# electrical_circut_clock.net
KiCad netlist of a schematic drawn in EAGLE
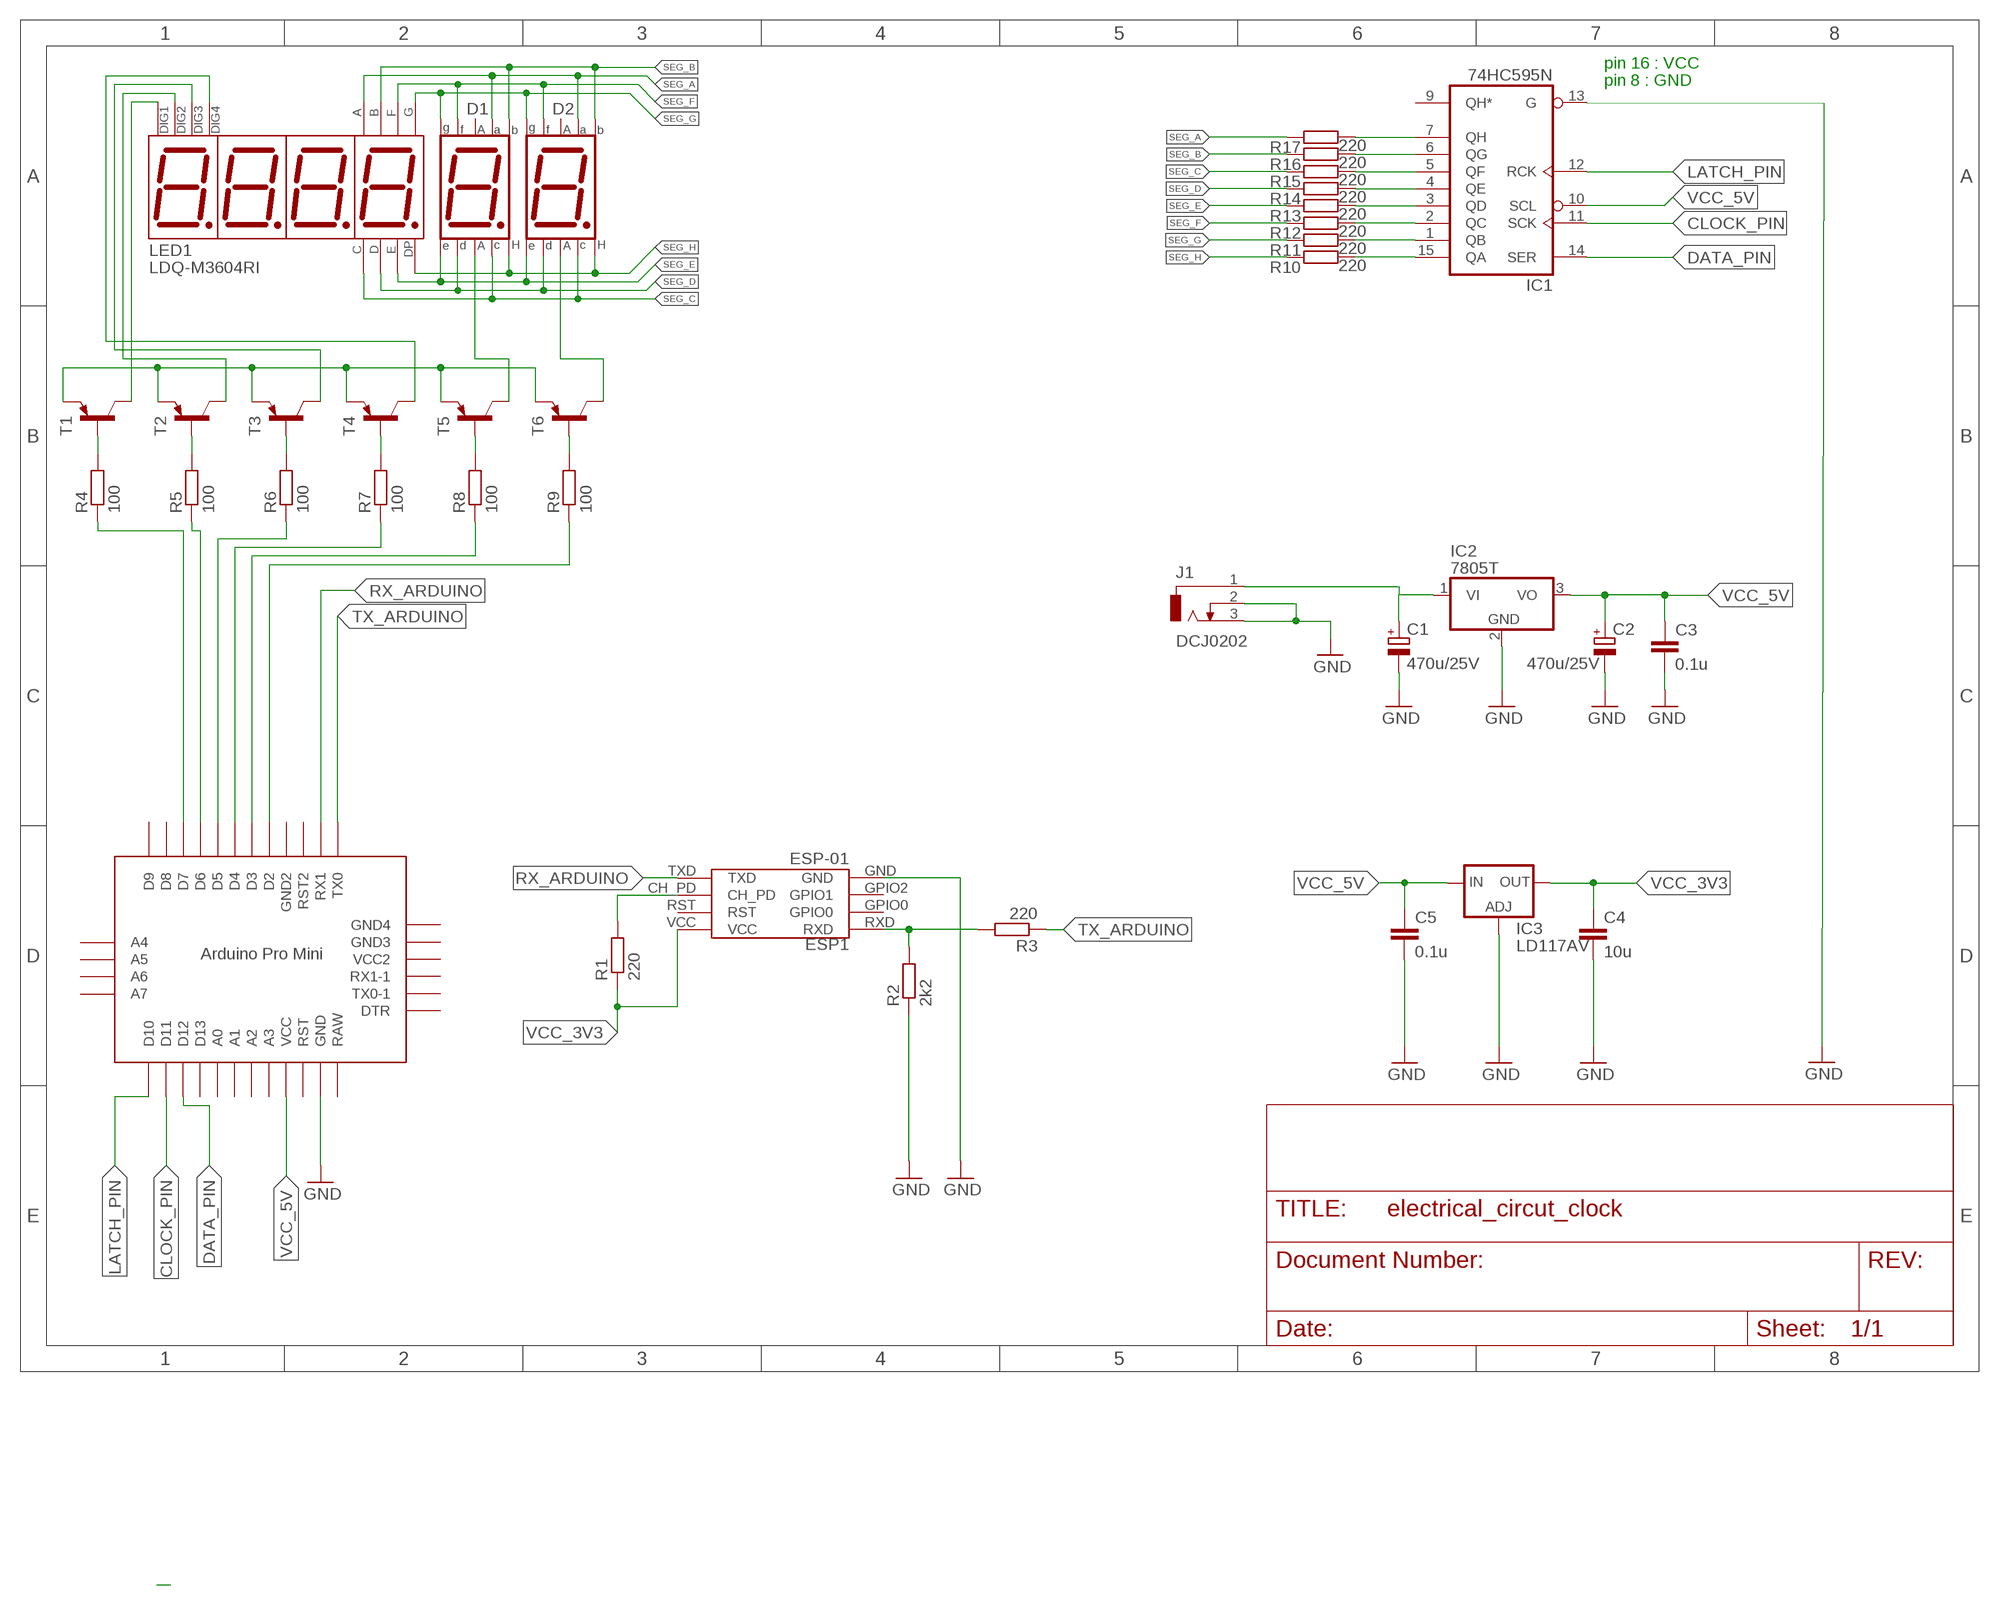
[diagram p0: schematic, sheet 1]

(export (version "E")
  (design (tool "Eeschema 10.0.6"))
  (components
    (comp (ref "C1")
      (value "470u/25V")
      (footprint "eagle-import:E5-8,5")
      (libsource (lib "eagle-import") (part "CPOL-EUE5-8.5"))
    )
    (comp (ref "C2")
      (value "470u/25V")
      (footprint "eagle-import:E5-8,5")
      (libsource (lib "eagle-import") (part "CPOL-EUE5-8.5"))
    )
    (comp (ref "C3")
      (value "0.1u")
      (footprint "eagle-import:C025-025X050")
      (libsource (lib "eagle-import") (part "C-EU025-025X050"))
    )
    (comp (ref "C4")
      (value "10u")
      (footprint "eagle-import:C025-025X050")
      (libsource (lib "eagle-import") (part "C-EU025-025X050"))
    )
    (comp (ref "C5")
      (value "0.1u")
      (footprint "eagle-import:C025-025X050")
      (libsource (lib "eagle-import") (part "C-EU025-025X050"))
    )
    (comp (ref "D1")
      (value "7SEG-CA")
      (footprint "eagle-import:7SEG-13")
      (libsource (lib "eagle-import") (part "7SEG-CA"))
    )
    (comp (ref "D2")
      (value "7SEG-CA")
      (footprint "eagle-import:7SEG-13")
      (libsource (lib "eagle-import") (part "7SEG-CA"))
    )
    (comp (ref "ESP1")
      (value "ESP-01")
      (footprint "eagle-import:ESP-01")
      (fields (field (name "MF") "AI-Thinker"))
      (libsource (lib "eagle-import") (part "ESP-01"))
    )
    (comp (ref "IC1")
      (value "74HC595N")
      (footprint "eagle-import:DIL16")
      (libsource (lib "eagle-import") (part "74595NHC"))
    )
    (comp (ref "IC2")
      (value "7805T")
      (footprint "eagle-import:TO220H")
      (libsource (lib "eagle-import") (part "78T05"))
    )
    (comp (ref "IC3")
      (value "LD117AV")
      (footprint "eagle-import:TO220L1")
      (libsource (lib "eagle-import") (part "LD117A?V"))
    )
    (comp (ref "J1")
      (value "DCJ0202")
      (footprint "eagle-import:DCJ0202")
      (libsource (lib "eagle-import") (part "DCJ0202"))
    )
    (comp (ref "LED1")
      (value "LDQ-M3604RI")
      (footprint "eagle-import:LDQ-M3604RI")
      (fields (field (name "MF") "Lumex"))
      (libsource (lib "eagle-import") (part "LDQ-M3604RI"))
    )
    (comp (ref "R1")
      (value "220")
      (footprint "eagle-import:0204_7")
      (libsource (lib "eagle-import") (part "R-EU_0204/7"))
    )
    (comp (ref "R2")
      (value "2k2")
      (footprint "eagle-import:0204_7")
      (libsource (lib "eagle-import") (part "R-EU_0204/7"))
    )
    (comp (ref "R3")
      (value "220")
      (footprint "eagle-import:0204_7")
      (libsource (lib "eagle-import") (part "R-EU_0204/7"))
    )
    (comp (ref "R4")
      (value "100")
      (footprint "eagle-import:0204_7")
      (libsource (lib "eagle-import") (part "R-EU_0204/7"))
    )
    (comp (ref "R5")
      (value "100")
      (footprint "eagle-import:0204_7")
      (libsource (lib "eagle-import") (part "R-EU_0204/7"))
    )
    (comp (ref "R6")
      (value "100")
      (footprint "eagle-import:0204_7")
      (libsource (lib "eagle-import") (part "R-EU_0204/7"))
    )
    (comp (ref "R7")
      (value "100")
      (footprint "eagle-import:0204_7")
      (libsource (lib "eagle-import") (part "R-EU_0204/7"))
    )
    (comp (ref "R8")
      (value "100")
      (footprint "eagle-import:0204_7")
      (libsource (lib "eagle-import") (part "R-EU_0204/7"))
    )
    (comp (ref "R9")
      (value "100")
      (footprint "eagle-import:0204_7")
      (libsource (lib "eagle-import") (part "R-EU_0204/7"))
    )
    (comp (ref "R10")
      (value "220")
      (footprint "eagle-import:0204_7")
      (libsource (lib "eagle-import") (part "R-EU_0204/7"))
    )
    (comp (ref "R11")
      (value "220")
      (footprint "eagle-import:0204_7")
      (libsource (lib "eagle-import") (part "R-EU_0204/7"))
    )
    (comp (ref "R12")
      (value "220")
      (footprint "eagle-import:0204_7")
      (libsource (lib "eagle-import") (part "R-EU_0204/7"))
    )
    (comp (ref "R13")
      (value "220")
      (footprint "eagle-import:0204_7")
      (libsource (lib "eagle-import") (part "R-EU_0204/7"))
    )
    (comp (ref "R14")
      (value "220")
      (footprint "eagle-import:0204_7")
      (libsource (lib "eagle-import") (part "R-EU_0204/7"))
    )
    (comp (ref "R15")
      (value "220")
      (footprint "eagle-import:0204_7")
      (libsource (lib "eagle-import") (part "R-EU_0204/7"))
    )
    (comp (ref "R16")
      (value "220")
      (footprint "eagle-import:0204_7")
      (libsource (lib "eagle-import") (part "R-EU_0204/7"))
    )
    (comp (ref "R17")
      (value "220")
      (footprint "eagle-import:0204_7")
      (libsource (lib "eagle-import") (part "R-EU_0204/7"))
    )
    (comp (ref "T1")
      (value "BC556A-PNP-TO92-EBC")
      (footprint "eagle-import:TO92-EBC")
      (libsource (lib "eagle-import") (part "-PNP-TO92-EBCBC556A"))
    )
    (comp (ref "T2")
      (value "BC556A-PNP-TO92-EBC")
      (footprint "eagle-import:TO92-EBC")
      (libsource (lib "eagle-import") (part "-PNP-TO92-EBCBC556A"))
    )
    (comp (ref "T3")
      (value "BC556A-PNP-TO92-EBC")
      (footprint "eagle-import:TO92-EBC")
      (libsource (lib "eagle-import") (part "-PNP-TO92-EBCBC556A"))
    )
    (comp (ref "T4")
      (value "BC556A-PNP-TO92-EBC")
      (footprint "eagle-import:TO92-EBC")
      (libsource (lib "eagle-import") (part "-PNP-TO92-EBCBC556A"))
    )
    (comp (ref "T5")
      (value "BC556A-PNP-TO92-EBC")
      (footprint "eagle-import:TO92-EBC")
      (libsource (lib "eagle-import") (part "-PNP-TO92-EBCBC556A"))
    )
    (comp (ref "T6")
      (value "BC556A-PNP-TO92-EBC")
      (footprint "eagle-import:TO92-EBC")
      (libsource (lib "eagle-import") (part "-PNP-TO92-EBCBC556A"))
    )
    (comp (ref "U$1")
      (value "PRO-MINI")
      (footprint "eagle-import:PRO-MINI")
      (libsource (lib "eagle-import") (part "PRO-MINI"))
    )
  )
  (nets
    (net (code "1") (name "/RAW") (class "Default")
      (node (ref "U$1") (pin "RAW") (pinfunction "RAW_RAW") (pintype "power_in"))
    )
    (net (code "2") (name "CLOCK_PIN") (class "Default")
      (node (ref "IC1") (pin "11") (pinfunction "SCK_11") (pintype "input"))
      (node (ref "U$1") (pin "D11") (pinfunction "D11_D11") (pintype "bidirectional"))
    )
    (net (code "3") (name "DATA_PIN") (class "Default")
      (node (ref "IC1") (pin "14") (pinfunction "SER_14") (pintype "input"))
      (node (ref "U$1") (pin "D12") (pinfunction "D12_D12") (pintype "bidirectional"))
    )
    (net (code "4") (name "GND") (class "Default")
      (node (ref "C1") (pin "-") (pinfunction "-_-") (pintype "passive"))
      (node (ref "C2") (pin "-") (pinfunction "-_-") (pintype "passive"))
      (node (ref "C3") (pin "2") (pinfunction "2_2") (pintype "passive"))
      (node (ref "C4") (pin "2") (pinfunction "2_2") (pintype "passive"))
      (node (ref "C5") (pin "2") (pinfunction "2_2") (pintype "passive"))
      (node (ref "ESP1") (pin "GND") (pinfunction "GND_GND") (pintype "bidirectional"))
      (node (ref "IC1") (pin "13") (pinfunction "G_13") (pintype "input"))
      (node (ref "IC2") (pin "2") (pinfunction "GND_2") (pintype "passive"))
      (node (ref "IC3") (pin "1") (pinfunction "ADJ_1") (pintype "input"))
      (node (ref "J1") (pin "2") (pinfunction "2_2") (pintype "passive"))
      (node (ref "J1") (pin "3") (pinfunction "3_3") (pintype "passive"))
      (node (ref "R2") (pin "1") (pinfunction "1_1") (pintype "passive"))
      (node (ref "U$1") (pin "GND") (pinfunction "GND_GND") (pintype "input"))
    )
    (net (code "5") (name "LATCH_PIN") (class "Default")
      (node (ref "IC1") (pin "12") (pinfunction "RCK_12") (pintype "input"))
      (node (ref "U$1") (pin "D10") (pinfunction "D10_D10") (pintype "bidirectional"))
    )
    (net (code "6") (name "Net-(D1-CA2)") (class "Default")
      (node (ref "D1") (pin "8") (pinfunction "CA2_8") (pintype "passive"))
      (node (ref "T5") (pin "C") (pinfunction "C_C") (pintype "passive"))
    )
    (net (code "7") (name "Net-(D2-CA2)") (class "Default")
      (node (ref "D2") (pin "8") (pinfunction "CA2_8") (pintype "passive"))
      (node (ref "T6") (pin "C") (pinfunction "C_C") (pintype "passive"))
    )
    (net (code "8") (name "Net-(ESP1-PadCH_PD)") (class "Default")
      (node (ref "ESP1") (pin "CH_PD") (pinfunction "CH_PD_CH_PD") (pintype "bidirectional"))
      (node (ref "R1") (pin "2") (pinfunction "2_2") (pintype "passive"))
    )
    (net (code "9") (name "Net-(IC1A-QA)") (class "Default")
      (node (ref "IC1") (pin "15") (pinfunction "QA_15") (pintype "tri_state"))
      (node (ref "R10") (pin "2") (pinfunction "2_2") (pintype "passive"))
    )
    (net (code "10") (name "Net-(IC1A-QB)") (class "Default")
      (node (ref "IC1") (pin "1") (pinfunction "QB_1") (pintype "tri_state"))
      (node (ref "R11") (pin "2") (pinfunction "2_2") (pintype "passive"))
    )
    (net (code "11") (name "Net-(IC1A-QC)") (class "Default")
      (node (ref "IC1") (pin "2") (pinfunction "QC_2") (pintype "tri_state"))
      (node (ref "R12") (pin "2") (pinfunction "2_2") (pintype "passive"))
    )
    (net (code "12") (name "Net-(IC1A-QD)") (class "Default")
      (node (ref "IC1") (pin "3") (pinfunction "QD_3") (pintype "tri_state"))
      (node (ref "R13") (pin "2") (pinfunction "2_2") (pintype "passive"))
    )
    (net (code "13") (name "Net-(IC1A-QE)") (class "Default")
      (node (ref "IC1") (pin "4") (pinfunction "QE_4") (pintype "tri_state"))
      (node (ref "R14") (pin "2") (pinfunction "2_2") (pintype "passive"))
    )
    (net (code "14") (name "Net-(IC1A-QF)") (class "Default")
      (node (ref "IC1") (pin "5") (pinfunction "QF_5") (pintype "tri_state"))
      (node (ref "R15") (pin "2") (pinfunction "2_2") (pintype "passive"))
    )
    (net (code "15") (name "Net-(IC1A-QG)") (class "Default")
      (node (ref "IC1") (pin "6") (pinfunction "QG_6") (pintype "tri_state"))
      (node (ref "R16") (pin "2") (pinfunction "2_2") (pintype "passive"))
    )
    (net (code "16") (name "Net-(IC1A-QH)") (class "Default")
      (node (ref "IC1") (pin "7") (pinfunction "QH_7") (pintype "tri_state"))
      (node (ref "R17") (pin "2") (pinfunction "2_2") (pintype "passive"))
    )
    (net (code "17") (name "Net-(IC2-VI)") (class "Default")
      (node (ref "C1") (pin "+") (pinfunction "+_+") (pintype "passive"))
      (node (ref "IC2") (pin "1") (pinfunction "VI_1") (pintype "input"))
      (node (ref "J1") (pin "1") (pinfunction "1_1") (pintype "passive"))
    )
    (net (code "18") (name "Net-(LED1-DIG1)") (class "Default")
      (node (ref "LED1") (pin "12") (pinfunction "DIG1_12") (pintype "bidirectional"))
      (node (ref "T1") (pin "C") (pinfunction "C_C") (pintype "passive"))
    )
    (net (code "19") (name "Net-(LED1-DIG2)") (class "Default")
      (node (ref "LED1") (pin "9") (pinfunction "DIG2_9") (pintype "bidirectional"))
      (node (ref "T2") (pin "C") (pinfunction "C_C") (pintype "passive"))
    )
    (net (code "20") (name "Net-(LED1-DIG3)") (class "Default")
      (node (ref "LED1") (pin "8") (pinfunction "DIG3_8") (pintype "bidirectional"))
      (node (ref "T3") (pin "C") (pinfunction "C_C") (pintype "passive"))
    )
    (net (code "21") (name "Net-(LED1-DIG4)") (class "Default")
      (node (ref "LED1") (pin "6") (pinfunction "DIG4_6") (pintype "bidirectional"))
      (node (ref "T4") (pin "C") (pinfunction "C_C") (pintype "passive"))
    )
    (net (code "22") (name "Net-(R4-Pad1)") (class "Default")
      (node (ref "R4") (pin "1") (pinfunction "1_1") (pintype "passive"))
      (node (ref "U$1") (pin "D7") (pinfunction "D7_D7") (pintype "bidirectional"))
    )
    (net (code "23") (name "Net-(R4-Pad2)") (class "Default")
      (node (ref "R4") (pin "2") (pinfunction "2_2") (pintype "passive"))
      (node (ref "T1") (pin "B") (pinfunction "B_B") (pintype "passive"))
    )
    (net (code "24") (name "Net-(R5-Pad1)") (class "Default")
      (node (ref "R5") (pin "1") (pinfunction "1_1") (pintype "passive"))
      (node (ref "U$1") (pin "D6") (pinfunction "D6_D6") (pintype "bidirectional"))
    )
    (net (code "25") (name "Net-(R5-Pad2)") (class "Default")
      (node (ref "R5") (pin "2") (pinfunction "2_2") (pintype "passive"))
      (node (ref "T2") (pin "B") (pinfunction "B_B") (pintype "passive"))
    )
    (net (code "26") (name "Net-(R6-Pad1)") (class "Default")
      (node (ref "R6") (pin "1") (pinfunction "1_1") (pintype "passive"))
      (node (ref "U$1") (pin "D5") (pinfunction "D5_D5") (pintype "bidirectional"))
    )
    (net (code "27") (name "Net-(R6-Pad2)") (class "Default")
      (node (ref "R6") (pin "2") (pinfunction "2_2") (pintype "passive"))
      (node (ref "T3") (pin "B") (pinfunction "B_B") (pintype "passive"))
    )
    (net (code "28") (name "Net-(R7-Pad1)") (class "Default")
      (node (ref "R7") (pin "1") (pinfunction "1_1") (pintype "passive"))
      (node (ref "U$1") (pin "D4") (pinfunction "D4_D4") (pintype "bidirectional"))
    )
    (net (code "29") (name "Net-(R7-Pad2)") (class "Default")
      (node (ref "R7") (pin "2") (pinfunction "2_2") (pintype "passive"))
      (node (ref "T4") (pin "B") (pinfunction "B_B") (pintype "passive"))
    )
    (net (code "30") (name "Net-(R8-Pad1)") (class "Default")
      (node (ref "R8") (pin "1") (pinfunction "1_1") (pintype "passive"))
      (node (ref "U$1") (pin "D3") (pinfunction "D3_D3") (pintype "bidirectional"))
    )
    (net (code "31") (name "Net-(R8-Pad2)") (class "Default")
      (node (ref "R8") (pin "2") (pinfunction "2_2") (pintype "passive"))
      (node (ref "T5") (pin "B") (pinfunction "B_B") (pintype "passive"))
    )
    (net (code "32") (name "Net-(R9-Pad1)") (class "Default")
      (node (ref "R9") (pin "1") (pinfunction "1_1") (pintype "passive"))
      (node (ref "U$1") (pin "D2") (pinfunction "D2_D2") (pintype "bidirectional"))
    )
    (net (code "33") (name "Net-(R9-Pad2)") (class "Default")
      (node (ref "R9") (pin "2") (pinfunction "2_2") (pintype "passive"))
      (node (ref "T6") (pin "B") (pinfunction "B_B") (pintype "passive"))
    )
    (net (code "34") (name "Net-(T1-PadE)") (class "Default")
      (node (ref "T1") (pin "E") (pinfunction "E_E") (pintype "passive"))
      (node (ref "T2") (pin "E") (pinfunction "E_E") (pintype "passive"))
      (node (ref "T3") (pin "E") (pinfunction "E_E") (pintype "passive"))
      (node (ref "T4") (pin "E") (pinfunction "E_E") (pintype "passive"))
      (node (ref "T5") (pin "E") (pinfunction "E_E") (pintype "passive"))
      (node (ref "T6") (pin "E") (pinfunction "E_E") (pintype "passive"))
    )
    (net (code "35") (name "RX_ARDUINO") (class "Default")
      (node (ref "ESP1") (pin "TXD") (pinfunction "TXD_TXD") (pintype "bidirectional"))
      (node (ref "U$1") (pin "RX1") (pinfunction "RX1_RX1") (pintype "bidirectional"))
    )
    (net (code "36") (name "SEG_A") (class "Default")
      (node (ref "D1") (pin "7") (pinfunction "A_7") (pintype "passive"))
      (node (ref "D2") (pin "7") (pinfunction "A_7") (pintype "passive"))
      (node (ref "LED1") (pin "11") (pinfunction "A_11") (pintype "bidirectional"))
      (node (ref "R17") (pin "1") (pinfunction "1_1") (pintype "passive"))
    )
    (net (code "37") (name "SEG_B") (class "Default")
      (node (ref "D1") (pin "6") (pinfunction "B_6") (pintype "passive"))
      (node (ref "D2") (pin "6") (pinfunction "B_6") (pintype "passive"))
      (node (ref "LED1") (pin "7") (pinfunction "B_7") (pintype "bidirectional"))
      (node (ref "R16") (pin "1") (pinfunction "1_1") (pintype "passive"))
    )
    (net (code "38") (name "SEG_C") (class "Default")
      (node (ref "D1") (pin "4") (pinfunction "C_4") (pintype "passive"))
      (node (ref "D2") (pin "4") (pinfunction "C_4") (pintype "passive"))
      (node (ref "LED1") (pin "4") (pinfunction "C_4") (pintype "bidirectional"))
      (node (ref "R15") (pin "1") (pinfunction "1_1") (pintype "passive"))
    )
    (net (code "39") (name "SEG_D") (class "Default")
      (node (ref "D1") (pin "2") (pinfunction "D_2") (pintype "passive"))
      (node (ref "D2") (pin "2") (pinfunction "D_2") (pintype "passive"))
      (node (ref "LED1") (pin "2") (pinfunction "D_2") (pintype "bidirectional"))
      (node (ref "R14") (pin "1") (pinfunction "1_1") (pintype "passive"))
    )
    (net (code "40") (name "SEG_E") (class "Default")
      (node (ref "D1") (pin "1") (pinfunction "E_1") (pintype "passive"))
      (node (ref "D2") (pin "1") (pinfunction "E_1") (pintype "passive"))
      (node (ref "LED1") (pin "1") (pinfunction "E_1") (pintype "bidirectional"))
      (node (ref "R13") (pin "1") (pinfunction "1_1") (pintype "passive"))
    )
    (net (code "41") (name "SEG_F") (class "Default")
      (node (ref "D1") (pin "9") (pinfunction "F_9") (pintype "passive"))
      (node (ref "D2") (pin "9") (pinfunction "F_9") (pintype "passive"))
      (node (ref "LED1") (pin "10") (pinfunction "F_10") (pintype "bidirectional"))
      (node (ref "R12") (pin "1") (pinfunction "1_1") (pintype "passive"))
    )
    (net (code "42") (name "SEG_G") (class "Default")
      (node (ref "D1") (pin "10") (pinfunction "G_10") (pintype "passive"))
      (node (ref "D2") (pin "10") (pinfunction "G_10") (pintype "passive"))
      (node (ref "LED1") (pin "5") (pinfunction "G_5") (pintype "bidirectional"))
      (node (ref "R11") (pin "1") (pinfunction "1_1") (pintype "passive"))
    )
    (net (code "43") (name "SEG_H") (class "Default")
      (node (ref "D1") (pin "5") (pinfunction "DP_5") (pintype "passive"))
      (node (ref "D2") (pin "5") (pinfunction "DP_5") (pintype "passive"))
      (node (ref "LED1") (pin "3") (pinfunction "DP_3") (pintype "bidirectional"))
      (node (ref "R10") (pin "1") (pinfunction "1_1") (pintype "passive"))
    )
    (net (code "44") (name "TX_ARDUINO") (class "Default")
      (node (ref "ESP1") (pin "RXD") (pinfunction "RXD_RXD") (pintype "bidirectional"))
      (node (ref "R2") (pin "2") (pinfunction "2_2") (pintype "passive"))
      (node (ref "R3") (pin "1") (pinfunction "1_1") (pintype "passive"))
      (node (ref "R3") (pin "2") (pinfunction "2_2") (pintype "passive"))
      (node (ref "U$1") (pin "TX0") (pinfunction "TX0_TX0") (pintype "bidirectional"))
    )
    (net (code "45") (name "VCC_3V3") (class "Default")
      (node (ref "C4") (pin "1") (pinfunction "1_1") (pintype "passive"))
      (node (ref "ESP1") (pin "VCC") (pinfunction "VCC_VCC") (pintype "bidirectional"))
      (node (ref "IC3") (pin "2") (pinfunction "OUT_2") (pintype "passive"))
      (node (ref "R1") (pin "1") (pinfunction "1_1") (pintype "passive"))
    )
    (net (code "46") (name "VCC_5V") (class "Default")
      (node (ref "C2") (pin "+") (pinfunction "+_+") (pintype "passive"))
      (node (ref "C3") (pin "1") (pinfunction "1_1") (pintype "passive"))
      (node (ref "C5") (pin "1") (pinfunction "1_1") (pintype "passive"))
      (node (ref "IC1") (pin "10") (pinfunction "SCL_10") (pintype "input"))
      (node (ref "IC2") (pin "3") (pinfunction "VO_3") (pintype "passive"))
      (node (ref "IC3") (pin "3") (pinfunction "IN_3") (pintype "input"))
      (node (ref "U$1") (pin "VCC") (pinfunction "VCC_VCC") (pintype "bidirectional"))
    )
    (net (code "47") (name "unconnected-(D1-CA1-Pad3)") (class "Default")
      (node (ref "D1") (pin "3") (pinfunction "CA1_3") (pintype "passive"))
    )
    (net (code "48") (name "unconnected-(D2-CA1-Pad3)") (class "Default")
      (node (ref "D2") (pin "3") (pinfunction "CA1_3") (pintype "passive"))
    )
    (net (code "49") (name "unconnected-(ESP1-GPIO1-PadGPIO2)") (class "Default")
      (node (ref "ESP1") (pin "GPIO2") (pinfunction "GPIO1_GPIO2") (pintype "bidirectional"))
    )
    (net (code "50") (name "unconnected-(ESP1-PadGPIO0)") (class "Default")
      (node (ref "ESP1") (pin "GPIO0") (pinfunction "GPIO0_GPIO0") (pintype "bidirectional"))
    )
    (net (code "51") (name "unconnected-(ESP1-PadRST)") (class "Default")
      (node (ref "ESP1") (pin "RST") (pinfunction "RST_RST") (pintype "bidirectional"))
    )
    (net (code "52") (name "unconnected-(IC1A-QH*-Pad9)") (class "Default")
      (node (ref "IC1") (pin "9") (pinfunction "QH*_9") (pintype "tri_state"))
    )
    (net (code "53") (name "unconnected-(U$1-GND2-PadGND1)") (class "Default")
      (node (ref "U$1") (pin "GND1") (pinfunction "GND2_GND1") (pintype "bidirectional"))
    )
    (net (code "54") (name "unconnected-(U$1-GND4-PadGND2)") (class "Default")
      (node (ref "U$1") (pin "GND2") (pinfunction "GND4_GND2") (pintype "bidirectional"))
    )
    (net (code "55") (name "unconnected-(U$1-PadA0)") (class "Default")
      (node (ref "U$1") (pin "A0") (pinfunction "A0_A0") (pintype "bidirectional"))
    )
    (net (code "56") (name "unconnected-(U$1-PadA1)") (class "Default")
      (node (ref "U$1") (pin "A1") (pinfunction "A1_A1") (pintype "bidirectional"))
    )
    (net (code "57") (name "unconnected-(U$1-PadA2)") (class "Default")
      (node (ref "U$1") (pin "A2") (pinfunction "A2_A2") (pintype "bidirectional"))
    )
    (net (code "58") (name "unconnected-(U$1-PadA3)") (class "Default")
      (node (ref "U$1") (pin "A3") (pinfunction "A3_A3") (pintype "bidirectional"))
    )
    (net (code "59") (name "unconnected-(U$1-PadA4)") (class "Default")
      (node (ref "U$1") (pin "A4") (pinfunction "A4_A4") (pintype "bidirectional"))
    )
    (net (code "60") (name "unconnected-(U$1-PadA5)") (class "Default")
      (node (ref "U$1") (pin "A5") (pinfunction "A5_A5") (pintype "bidirectional"))
    )
    (net (code "61") (name "unconnected-(U$1-PadA6)") (class "Default")
      (node (ref "U$1") (pin "A6") (pinfunction "A6_A6") (pintype "bidirectional"))
    )
    (net (code "62") (name "unconnected-(U$1-PadA7)") (class "Default")
      (node (ref "U$1") (pin "A7") (pinfunction "A7_A7") (pintype "bidirectional"))
    )
    (net (code "63") (name "unconnected-(U$1-PadD8)") (class "Default")
      (node (ref "U$1") (pin "D8") (pinfunction "D8_D8") (pintype "bidirectional"))
    )
    (net (code "64") (name "unconnected-(U$1-PadD9)") (class "Default")
      (node (ref "U$1") (pin "D9") (pinfunction "D9_D9") (pintype "bidirectional"))
    )
    (net (code "65") (name "unconnected-(U$1-PadD13)") (class "Default")
      (node (ref "U$1") (pin "D13") (pinfunction "D13_D13") (pintype "bidirectional"))
    )
    (net (code "66") (name "unconnected-(U$1-PadDTR)") (class "Default")
      (node (ref "U$1") (pin "DTR") (pinfunction "DTR_DTR") (pintype "bidirectional"))
    )
    (net (code "67") (name "unconnected-(U$1-PadGND3)") (class "Default")
      (node (ref "U$1") (pin "GND3") (pinfunction "GND3_GND3") (pintype "bidirectional"))
    )
    (net (code "68") (name "unconnected-(U$1-PadRST)") (class "Default")
      (node (ref "U$1") (pin "RST") (pinfunction "RST_RST") (pintype "bidirectional"))
    )
    (net (code "69") (name "unconnected-(U$1-PadRX1-1)") (class "Default")
      (node (ref "U$1") (pin "RX1-1") (pinfunction "RX1-1_RX1-1") (pintype "bidirectional"))
    )
    (net (code "70") (name "unconnected-(U$1-PadTX0-1)") (class "Default")
      (node (ref "U$1") (pin "TX0-1") (pinfunction "TX0-1_TX0-1") (pintype "bidirectional"))
    )
    (net (code "71") (name "unconnected-(U$1-RST2-PadRST1)") (class "Default")
      (node (ref "U$1") (pin "RST1") (pinfunction "RST2_RST1") (pintype "bidirectional"))
    )
    (net (code "72") (name "unconnected-(U$1-VCC2-PadVCC1)") (class "Default")
      (node (ref "U$1") (pin "VCC1") (pinfunction "VCC2_VCC1") (pintype "bidirectional"))
    )
  )
)
